# zmk_dongle.net
KiCad netlist of a schematic drawn in EasyEDA Pro
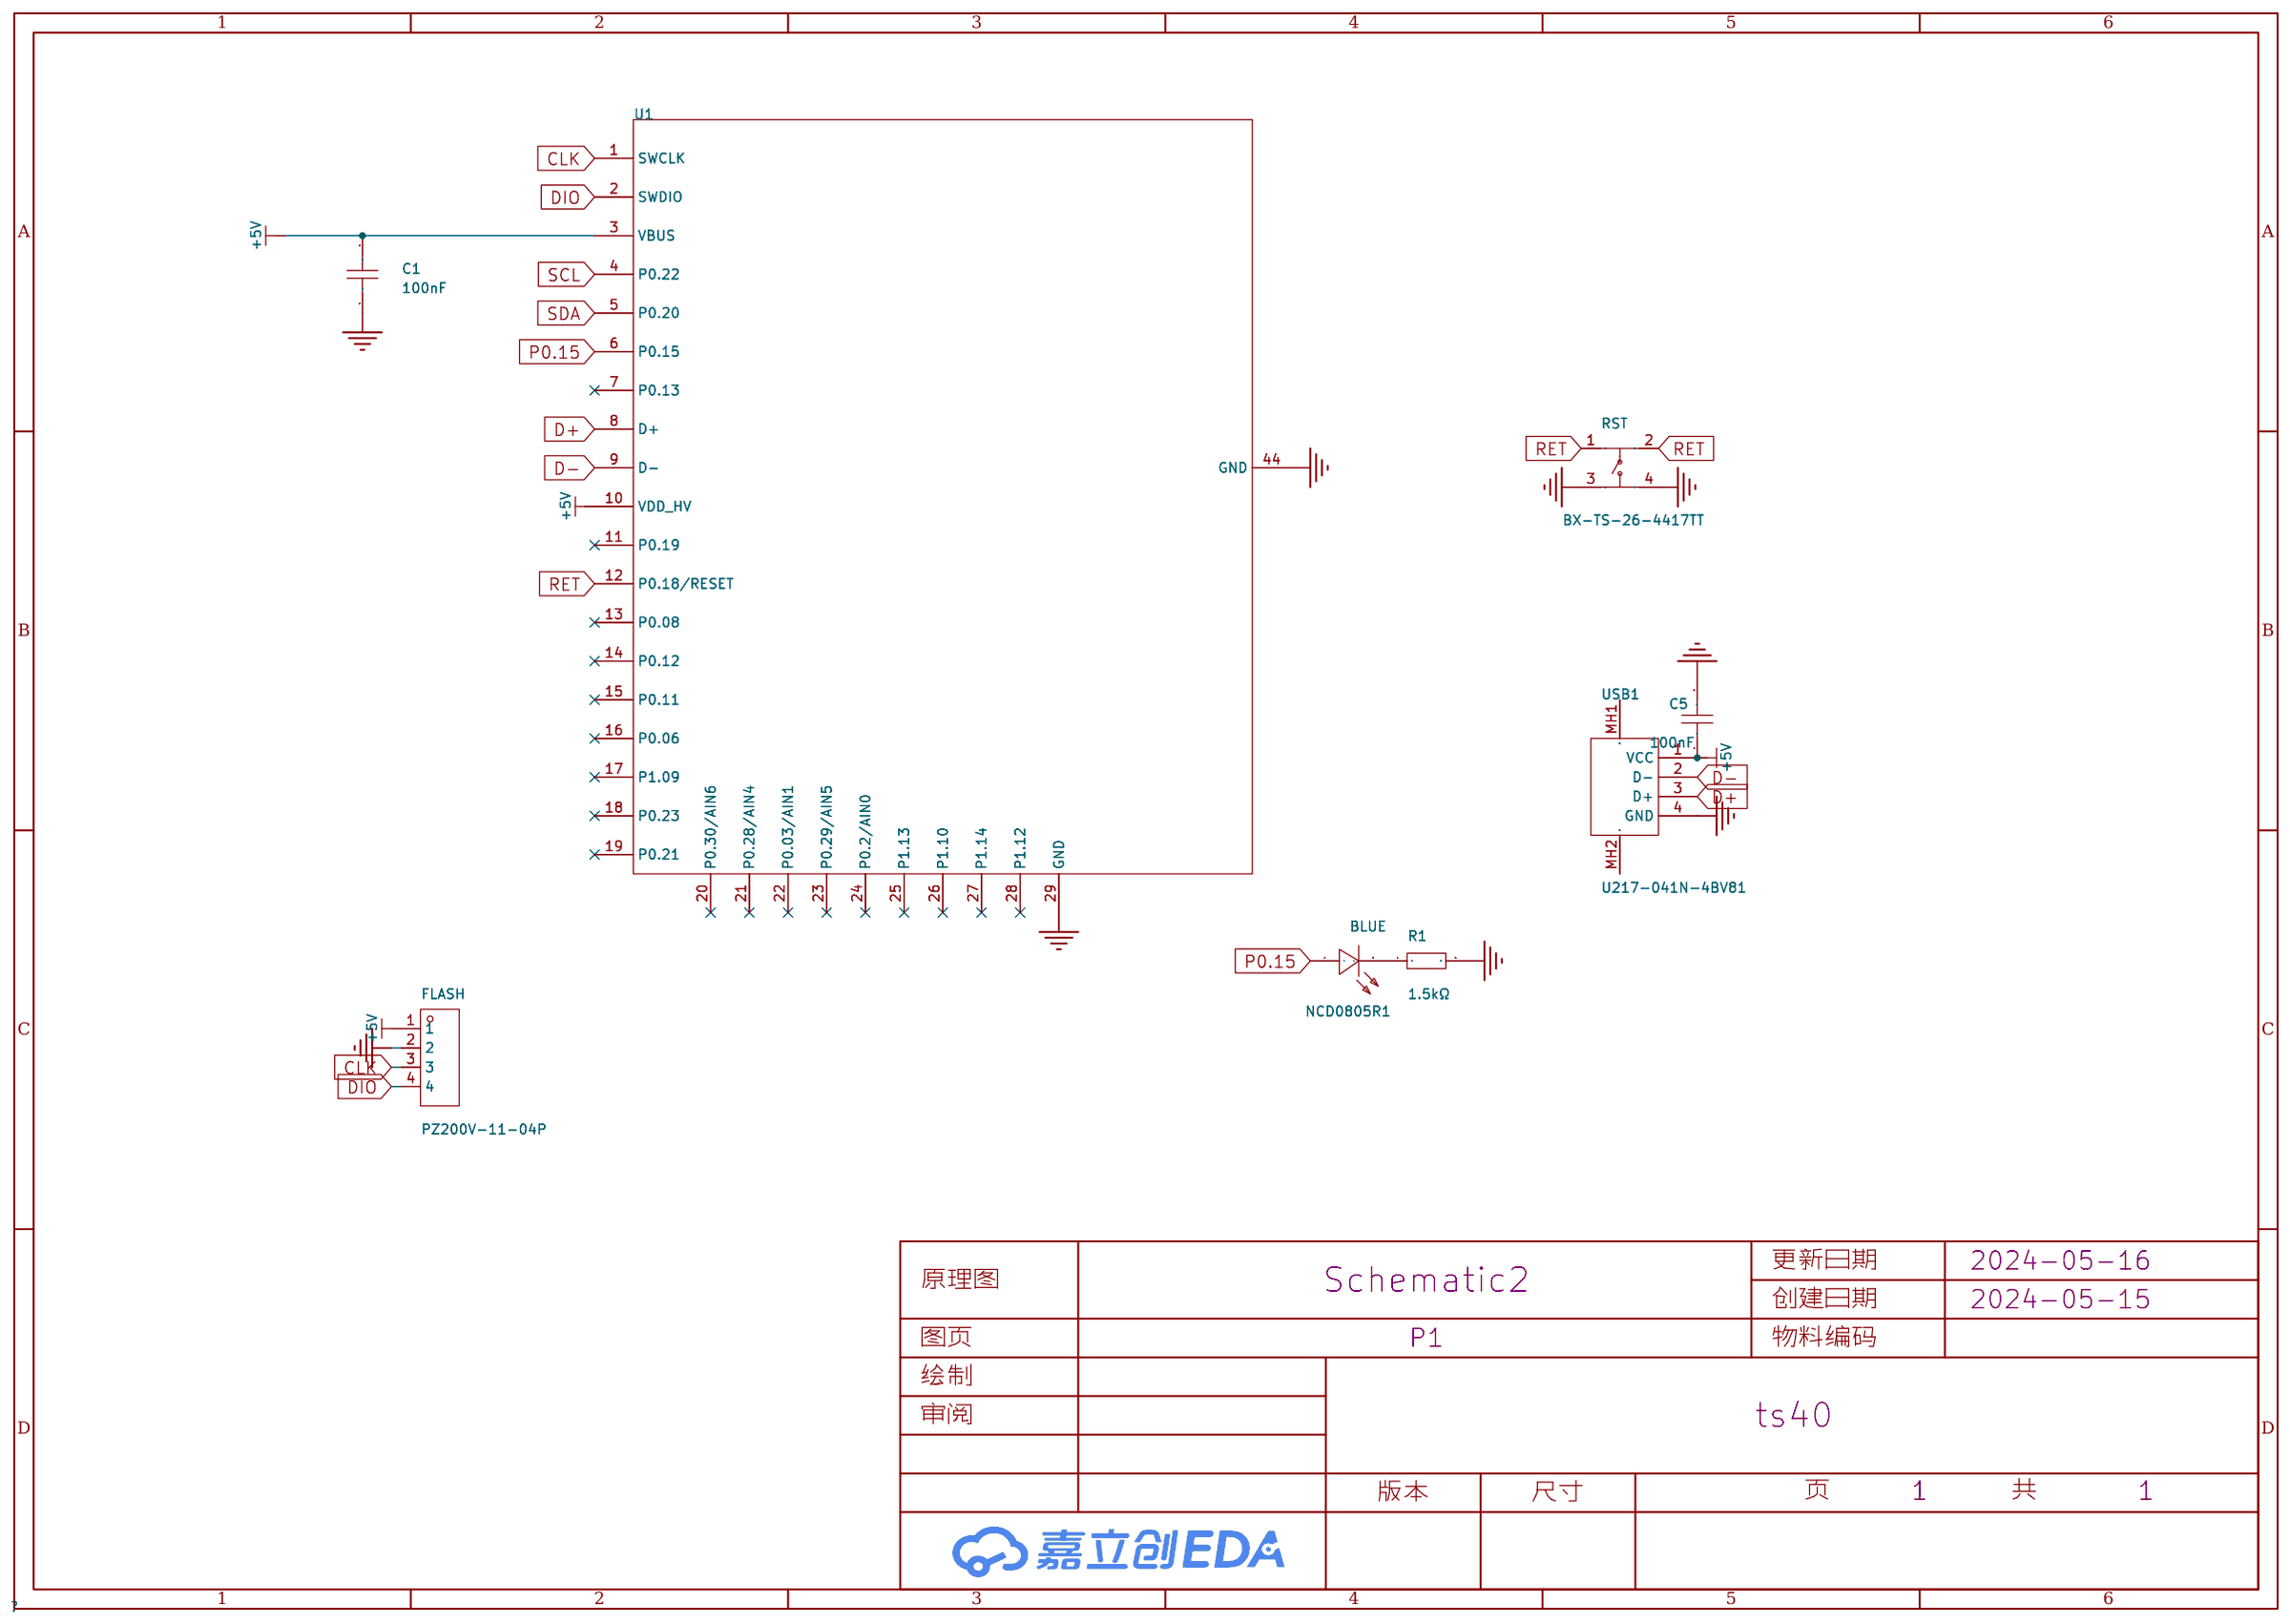
[diagram p0: schematic sheet]

(export (version "E")
  (design (tool "Eeschema 10.0.6"))
  (components
    (comp (ref "BLUE")
      (value "NCD0805R1")
      (footprint "easyedapro:LED0805-R-RD")
      (fields (field (name "Manufacturer") "国星光电"))
      (libsource (lib "easyedapro") (part "FC-2012HRK-620D"))
    )
    (comp (ref "C1")
      (value "100nF")
      (fields
        (field (name "Manufacturer Part") "CC0603KRX7R9BB104")
        (field (name "Manufacturer") "YAGEO(国巨)")
      )
      (libsource (lib "easyedapro") (part "CapAcitance"))
    )
    (comp (ref "C5")
      (value "100nF")
      (fields
        (field (name "Manufacturer Part") "CC0603KRX7R9BB104")
        (field (name "Manufacturer") "YAGEO(国巨)")
      )
      (libsource (lib "easyedapro") (part "CapAcitance"))
    )
    (comp (ref "FLASH")
      (value "PZ200V-11-04P")
      (footprint "easyedapro:HDR-TH_4P-P2.00-V-M")
      (fields (field (name "Manufacturer") "XFCN(兴飞)"))
      (libsource (lib "easyedapro") (part "PZ200V-11-04P"))
    )
    (comp (ref "R1")
      (value "1.5kΩ")
      (footprint "easyedapro:R0805")
      (description "电阻类型:厚膜电阻;阻值:1.5kΩ;精度:±1%;功率:125mW;最大工作电压:150V;温度系数:±100ppm/°C;")
      (fields
        (field (name "Manufacturer Part") "0805W8F1501T5E")
        (field (name "Manufacturer") "UNI-ROYAL(厚声)")
      )
      (libsource (lib "easyedapro") (part "0805W8F1501T5E"))
    )
    (comp (ref "RST")
      (value "BX-TS-26-4417TT")
      (footprint "easyedapro:SW-SMD_4P-L5.2-W5.2-P3.70-LS6.5")
      (fields (field (name "Manufacturer") "Bossie(博锡)"))
      (libsource (lib "easyedapro") (part "BX-TS-26-4417TT"))
    )
    (comp (ref "U1")
      (value "N52840")
      (footprint "easyedapro:52840MICRO-v1")
      (libsource (lib "easyedapro") (part "52840micro"))
    )
    (comp (ref "USB1")
      (value "U217-041N-4BV81")
      (fields (field (name "Manufacturer") "XKB Connectivity(中国星坤)"))
      (libsource (lib "easyedapro") (part "AM90"))
    )
  )
  (nets
    (net (code "1") (name "+5V") (class "Default")
      (node (ref "C1") (pin "2") (pinfunction "2_2") (pintype "input"))
      (node (ref "C5") (pin "1") (pinfunction "1_1") (pintype "input"))
      (node (ref "FLASH") (pin "1") (pinfunction "1_1") (pintype "unspecified"))
      (node (ref "U1") (pin "10") (pinfunction "VDD_HV_10") (pintype "input"))
      (node (ref "U1") (pin "3") (pinfunction "VBUS_3") (pintype "input"))
      (node (ref "USB1") (pin "1") (pinfunction "VCC_1") (pintype "input"))
    )
    (net (code "2") (name "CLK") (class "Default")
      (node (ref "FLASH") (pin "3") (pinfunction "3_3") (pintype "unspecified"))
      (node (ref "U1") (pin "1") (pinfunction "SWCLK_1") (pintype "input"))
    )
    (net (code "3") (name "D+") (class "Default")
      (node (ref "U1") (pin "8") (pinfunction "D+_8") (pintype "input"))
      (node (ref "USB1") (pin "3") (pinfunction "D+_3") (pintype "input"))
    )
    (net (code "4") (name "D-") (class "Default")
      (node (ref "U1") (pin "9") (pinfunction "D-_9") (pintype "input"))
      (node (ref "USB1") (pin "2") (pinfunction "D-_2") (pintype "input"))
    )
    (net (code "5") (name "DIO") (class "Default")
      (node (ref "FLASH") (pin "4") (pinfunction "4_4") (pintype "unspecified"))
      (node (ref "U1") (pin "2") (pinfunction "SWDIO_2") (pintype "input"))
    )
    (net (code "6") (name "GND") (class "Default")
      (node (ref "C1") (pin "1") (pinfunction "1_1") (pintype "input"))
      (node (ref "C5") (pin "2") (pinfunction "2_2") (pintype "input"))
      (node (ref "FLASH") (pin "2") (pinfunction "2_2") (pintype "unspecified"))
      (node (ref "R1") (pin "2") (pinfunction "2_2") (pintype "input"))
      (node (ref "RST") (pin "3") (pinfunction "3_3") (pintype "unspecified"))
      (node (ref "RST") (pin "4") (pinfunction "4_4") (pintype "unspecified"))
      (node (ref "U1") (pin "29") (pinfunction "GND_29") (pintype "input"))
      (node (ref "U1") (pin "44") (pinfunction "GND_44") (pintype "input"))
      (node (ref "USB1") (pin "4") (pinfunction "GND_4") (pintype "input"))
    )
    (net (code "7") (name "Net-(BLUE--)") (class "Default")
      (node (ref "BLUE") (pin "2") (pinfunction "-_2") (pintype "unspecified"))
      (node (ref "R1") (pin "1") (pinfunction "1_1") (pintype "input"))
    )
    (net (code "8") (name "P0.15") (class "Default")
      (node (ref "BLUE") (pin "1") (pinfunction "+_1") (pintype "unspecified"))
      (node (ref "U1") (pin "6") (pinfunction "P0.15_6") (pintype "input"))
    )
    (net (code "9") (name "RET") (class "Default")
      (node (ref "RST") (pin "1") (pinfunction "1_1") (pintype "unspecified"))
      (node (ref "RST") (pin "2") (pinfunction "2_2") (pintype "unspecified"))
      (node (ref "U1") (pin "12") (pinfunction "P0.18/RESET_12") (pintype "input"))
    )
    (net (code "10") (name "SCL") (class "Default")
      (node (ref "U1") (pin "4") (pinfunction "P0.22_4") (pintype "input"))
    )
    (net (code "11") (name "SDA") (class "Default")
      (node (ref "U1") (pin "5") (pinfunction "P0.20_5") (pintype "input"))
    )
    (net (code "12") (name "unconnected-(U1-P0.2{slash}AIN0-Pad24)") (class "Default")
      (node (ref "U1") (pin "24") (pinfunction "P0.2/AIN0_24") (pintype "input+no_connect"))
    )
    (net (code "13") (name "unconnected-(U1-P0.03{slash}AIN1-Pad22)") (class "Default")
      (node (ref "U1") (pin "22") (pinfunction "P0.03/AIN1_22") (pintype "input+no_connect"))
    )
    (net (code "14") (name "unconnected-(U1-P0.06-Pad16)") (class "Default")
      (node (ref "U1") (pin "16") (pinfunction "P0.06_16") (pintype "input+no_connect"))
    )
    (net (code "15") (name "unconnected-(U1-P0.08-Pad13)") (class "Default")
      (node (ref "U1") (pin "13") (pinfunction "P0.08_13") (pintype "input+no_connect"))
    )
    (net (code "16") (name "unconnected-(U1-P0.11-Pad15)") (class "Default")
      (node (ref "U1") (pin "15") (pinfunction "P0.11_15") (pintype "input+no_connect"))
    )
    (net (code "17") (name "unconnected-(U1-P0.12-Pad14)") (class "Default")
      (node (ref "U1") (pin "14") (pinfunction "P0.12_14") (pintype "input+no_connect"))
    )
    (net (code "18") (name "unconnected-(U1-P0.13-Pad7)") (class "Default")
      (node (ref "U1") (pin "7") (pinfunction "P0.13_7") (pintype "input+no_connect"))
    )
    (net (code "19") (name "unconnected-(U1-P0.19-Pad11)") (class "Default")
      (node (ref "U1") (pin "11") (pinfunction "P0.19_11") (pintype "input+no_connect"))
    )
    (net (code "20") (name "unconnected-(U1-P0.21-Pad19)") (class "Default")
      (node (ref "U1") (pin "19") (pinfunction "P0.21_19") (pintype "input+no_connect"))
    )
    (net (code "21") (name "unconnected-(U1-P0.23-Pad18)") (class "Default")
      (node (ref "U1") (pin "18") (pinfunction "P0.23_18") (pintype "input+no_connect"))
    )
    (net (code "22") (name "unconnected-(U1-P0.28{slash}AIN4-Pad21)") (class "Default")
      (node (ref "U1") (pin "21") (pinfunction "P0.28/AIN4_21") (pintype "input+no_connect"))
    )
    (net (code "23") (name "unconnected-(U1-P0.29{slash}AIN5-Pad23)") (class "Default")
      (node (ref "U1") (pin "23") (pinfunction "P0.29/AIN5_23") (pintype "input+no_connect"))
    )
    (net (code "24") (name "unconnected-(U1-P0.30{slash}AIN6-Pad20)") (class "Default")
      (node (ref "U1") (pin "20") (pinfunction "P0.30/AIN6_20") (pintype "input+no_connect"))
    )
    (net (code "25") (name "unconnected-(U1-P1.09-Pad17)") (class "Default")
      (node (ref "U1") (pin "17") (pinfunction "P1.09_17") (pintype "input+no_connect"))
    )
    (net (code "26") (name "unconnected-(U1-P1.10-Pad26)") (class "Default")
      (node (ref "U1") (pin "26") (pinfunction "P1.10_26") (pintype "input+no_connect"))
    )
    (net (code "27") (name "unconnected-(U1-P1.12-Pad28)") (class "Default")
      (node (ref "U1") (pin "28") (pinfunction "P1.12_28") (pintype "input+no_connect"))
    )
    (net (code "28") (name "unconnected-(U1-P1.13-Pad25)") (class "Default")
      (node (ref "U1") (pin "25") (pinfunction "P1.13_25") (pintype "input+no_connect"))
    )
    (net (code "29") (name "unconnected-(U1-P1.14-Pad27)") (class "Default")
      (node (ref "U1") (pin "27") (pinfunction "P1.14_27") (pintype "input+no_connect"))
    )
    (net (code "30") (name "unconnected-(USB1-PadMH1)") (class "Default")
      (node (ref "USB1") (pin "MH1") (pinfunction "MH1_MH1") (pintype "unspecified"))
    )
    (net (code "31") (name "unconnected-(USB1-PadMH2)") (class "Default")
      (node (ref "USB1") (pin "MH2") (pinfunction "MH2_MH2") (pintype "unspecified"))
    )
  )
)
